# Atmega328p-AU.net
KiCad netlist of a schematic drawn in Altium Designer
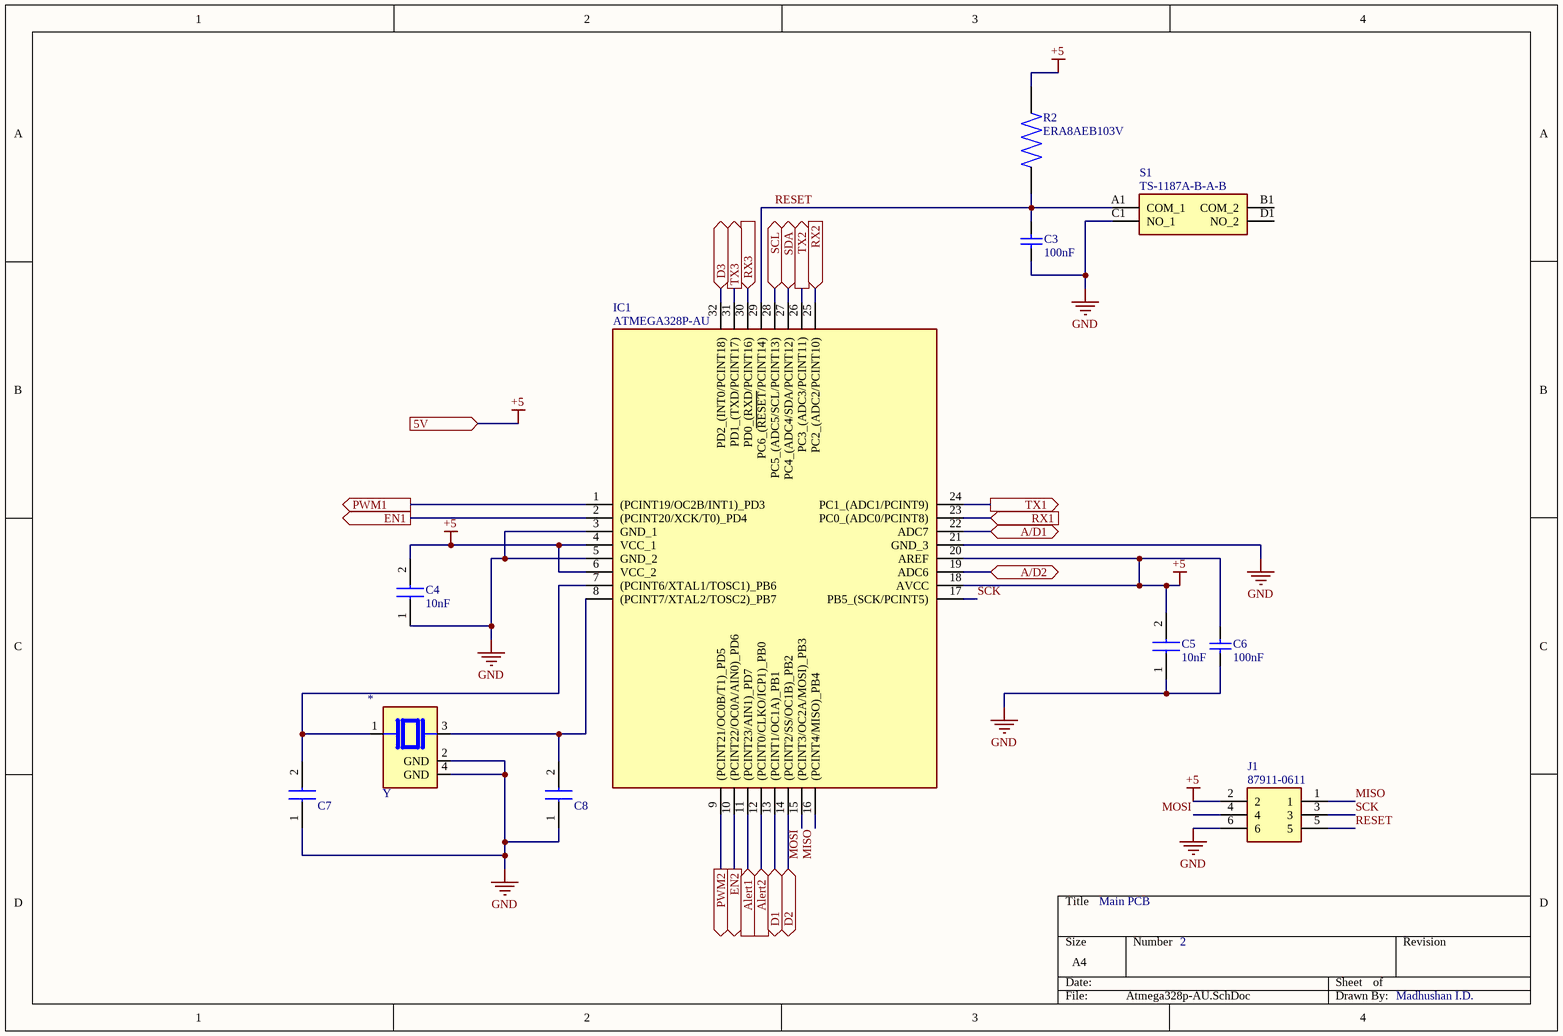
[diagram p0: Atmega328p-AU.SchDoc]

(export (version "E")
  (design (tool "Eeschema 10.0.6"))
  (components
    (comp (ref "C3")
      (value "1206GC102KAT1A")
      (footprint "AVX-1206-2_L")
      (description "Chip Capacitor, 1 nF, +/- 10%, -55 to 125 degC, 1206 (3216 Metric), RoHS, Tape and Reel")
      (fields
        (field (name "CAPACITANCE") "100nF")
        (field (name "TOLERANCE") "10%")
        (field (name "MANUFACTURER") "AVX")
      )
      (libsource (lib "Altium Content Vault") (part "CAP-NP-2"))
    )
    (comp (ref "C4")
      (value "10nF")
      (footprint "SamacSys:CAPC3216X94N")
      (description "Capacitor")
      (fields
        (field (name "MANUFACTURER_PART_NUMBER") "KAM31BR81H103KT")
        (field (name "MOUSER PART NUMBER") "581-KAM31BR81H103KT")
      )
      (libsource (lib "*") (part "KAM31BR81H103KT"))
    )
    (comp (ref "C5")
      (value "10nF")
      (footprint "SamacSys:CAPC3216X94N")
      (description "Capacitor")
      (fields
        (field (name "MANUFACTURER_PART_NUMBER") "KAM31BR81H103KT")
        (field (name "MOUSER PART NUMBER") "581-KAM31BR81H103KT")
      )
      (libsource (lib "*") (part "KAM31BR81H103KT"))
    )
    (comp (ref "C6")
      (value "1206GC102KAT1A")
      (footprint "AVX-1206-2_L")
      (description "Chip Capacitor, 1 nF, +/- 10%, -55 to 125 degC, 1206 (3216 Metric), RoHS, Tape and Reel")
      (fields
        (field (name "CAPACITANCE") "100nF")
        (field (name "TOLERANCE") "10%")
        (field (name "MANUFACTURER") "AVX")
      )
      (libsource (lib "Altium Content Vault") (part "CAP-NP-2"))
    )
    (comp (ref "C7")
      (value "C1206C220JGGACTU (22pF)")
      (footprint "SamacSys:C1206")
      (description "Capacitor")
      (fields
        (field (name "MANUFACTURER_PART_NUMBER") "C1206C220JGGACTU")
        (field (name "MOUSER PART NUMBER") "80-C1206C220JGG")
      )
      (libsource (lib "*") (part "C1206C220JGGACTU"))
    )
    (comp (ref "C8")
      (value "C1206C220JGGACTU (22pF)")
      (footprint "SamacSys:C1206")
      (description "Capacitor")
      (fields
        (field (name "MANUFACTURER_PART_NUMBER") "C1206C220JGGACTU")
        (field (name "MOUSER PART NUMBER") "80-C1206C220JGG")
      )
      (libsource (lib "*") (part "C1206C220JGGACTU"))
    )
    (comp (ref "IC1")
      (value "ATMEGA328P-AU")
      (footprint "SamacSys:QFP80P900X900X120-32N")
      (description "Integrated Circuit")
      (fields (field (name "MOUSER PART NUMBER") "556-ATMEGA328P-AU"))
      (libsource (lib "*") (part "ATMEGA328P-AU"))
    )
    (comp (ref "J1")
      (value "87911-0611")
      (footprint "SamacSys:879110611")
      (description "Connector")
      (fields (field (name "MOUSER PART NUMBER") "538-87911-0611"))
      (libsource (lib "SamacSys") (part "87911-0611"))
    )
    (comp (ref "R2")
      (value "ERA8AEB103V")
      (footprint "RES_ERA8AEB103V")
      (libsource (lib "ERA8AEB103V") (part "ERA8AEB103V"))
    )
    (comp (ref "S1")
      (value "TS-1187A-B-A-B")
      (footprint "SamacSys:TS1187ABAB")
      (description "Switch")
      (libsource (lib "*") (part "TS-1187A-B-A-B"))
    )
    (comp (ref "Y")
      (value "ABM11-16.000MHz-12-N1G-T")
      (footprint "XTAL_ABM11-16.000MHz-12-N1G-T")
      (fields (field (name "MF") "{'manufacturer': u'Abracon LLC'}") (field (name "16MHZ") "*"))
      (libsource (lib "ABM11-16.000MHz-12-N1G-T") (part "ABM11-16.000MHz-12-N1G-T"))
    )
  )
  (nets
    (net (code "1") (name "+5") (class "Default")
      (node (ref "C4") (pin "2") (pinfunction "2_2") (pintype "passive"))
      (node (ref "C5") (pin "2") (pinfunction "2_2") (pintype "passive"))
      (node (ref "C6") (pin "2") (pinfunction "2_2") (pintype "passive"))
      (node (ref "IC1") (pin "18") (pinfunction "AVCC_18") (pintype "passive"))
      (node (ref "IC1") (pin "20") (pinfunction "AREF_20") (pintype "passive"))
      (node (ref "IC1") (pin "4") (pinfunction "VCC_1_4") (pintype "passive"))
      (node (ref "IC1") (pin "6") (pinfunction "VCC_2_6") (pintype "passive"))
      (node (ref "J1") (pin "2") (pinfunction "2_2") (pintype "passive"))
      (node (ref "R2") (pin "2") (pinfunction "2_2") (pintype "passive"))
    )
    (net (code "2") (name "/Alert1") (class "Default")
      (node (ref "IC1") (pin "11") (pinfunction "(PCINT23/AIN1)_PD7_11") (pintype "passive"))
    )
    (net (code "3") (name "/Alert2") (class "Default")
      (node (ref "IC1") (pin "12") (pinfunction "(PCINT0/CLKO/ICP1)_PB0_12") (pintype "passive"))
    )
    (net (code "4") (name "/A{slash}D1") (class "Default")
      (node (ref "IC1") (pin "22") (pinfunction "ADC7_22") (pintype "passive"))
    )
    (net (code "5") (name "/A{slash}D2") (class "Default")
      (node (ref "IC1") (pin "19") (pinfunction "ADC6_19") (pintype "passive"))
    )
    (net (code "6") (name "/D1") (class "Default")
      (node (ref "IC1") (pin "13") (pinfunction "(PCINT1/OC1A)_PB1_13") (pintype "passive"))
    )
    (net (code "7") (name "/D2") (class "Default")
      (node (ref "IC1") (pin "14") (pinfunction "(PCINT2/SS/OC1B)_PB2_14") (pintype "passive"))
    )
    (net (code "8") (name "/D3") (class "Default")
      (node (ref "IC1") (pin "32") (pinfunction "PD2_(INT0/PCINT18)_32") (pintype "passive"))
    )
    (net (code "9") (name "/EN1") (class "Default")
      (node (ref "IC1") (pin "2") (pinfunction "(PCINT20/XCK/T0)_PD4_2") (pintype "passive"))
    )
    (net (code "10") (name "/EN2") (class "Default")
      (node (ref "IC1") (pin "10") (pinfunction "(PCINT22/OC0A/AIN0)_PD6_10") (pintype "passive"))
    )
    (net (code "11") (name "/MISO") (class "Default")
      (node (ref "IC1") (pin "16") (pinfunction "(PCINT4/MISO)_PB4_16") (pintype "passive"))
      (node (ref "J1") (pin "1") (pinfunction "1_1") (pintype "passive"))
    )
    (net (code "12") (name "/MOSI") (class "Default")
      (node (ref "IC1") (pin "15") (pinfunction "(PCINT3/OC2A/MOSI)_PB3_15") (pintype "passive"))
      (node (ref "J1") (pin "4") (pinfunction "4_4") (pintype "passive"))
    )
    (net (code "13") (name "/PWM1") (class "Default")
      (node (ref "IC1") (pin "1") (pinfunction "(PCINT19/OC2B/INT1)_PD3_1") (pintype "passive"))
    )
    (net (code "14") (name "/PWM2") (class "Default")
      (node (ref "IC1") (pin "9") (pinfunction "(PCINT21/OC0B/T1)_PD5_9") (pintype "passive"))
    )
    (net (code "15") (name "/RESET") (class "Default")
      (node (ref "C3") (pin "2") (pinfunction "2_2") (pintype "passive"))
      (node (ref "IC1") (pin "29") (pinfunction "PC6_(~{RESET}/PCINT14)_29") (pintype "passive"))
      (node (ref "J1") (pin "5") (pinfunction "5_5") (pintype "passive"))
      (node (ref "R2") (pin "1") (pinfunction "1_1") (pintype "passive"))
      (node (ref "S1") (pin "A1") (pinfunction "COM_1_A1") (pintype "passive"))
    )
    (net (code "16") (name "/RX1") (class "Default")
      (node (ref "IC1") (pin "23") (pinfunction "PC0_(ADC0/PCINT8)_23") (pintype "passive"))
    )
    (net (code "17") (name "/RX2") (class "Default")
      (node (ref "IC1") (pin "25") (pinfunction "PC2_(ADC2/PCINT10)_25") (pintype "passive"))
    )
    (net (code "18") (name "/RX3") (class "Default")
      (node (ref "IC1") (pin "30") (pinfunction "PD0_(RXD/PCINT16)_30") (pintype "passive"))
    )
    (net (code "19") (name "/SCK") (class "Default")
      (node (ref "IC1") (pin "17") (pinfunction "PB5_(SCK/PCINT5)_17") (pintype "passive"))
      (node (ref "J1") (pin "3") (pinfunction "3_3") (pintype "passive"))
    )
    (net (code "20") (name "/SCL") (class "Default")
      (node (ref "IC1") (pin "28") (pinfunction "PC5_(ADC5/SCL/PCINT13)_28") (pintype "passive"))
    )
    (net (code "21") (name "/SDA") (class "Default")
      (node (ref "IC1") (pin "27") (pinfunction "PC4_(ADC4/SDA/PCINT12)_27") (pintype "passive"))
    )
    (net (code "22") (name "/TX1") (class "Default")
      (node (ref "IC1") (pin "24") (pinfunction "PC1_(ADC1/PCINT9)_24") (pintype "passive"))
    )
    (net (code "23") (name "/TX2") (class "Default")
      (node (ref "IC1") (pin "26") (pinfunction "PC3_(ADC3/PCINT11)_26") (pintype "passive"))
    )
    (net (code "24") (name "/TX3") (class "Default")
      (node (ref "IC1") (pin "31") (pinfunction "PD1_(TXD/PCINT17)_31") (pintype "passive"))
    )
    (net (code "25") (name "GND") (class "Default")
      (node (ref "C3") (pin "1") (pinfunction "1_1") (pintype "passive"))
      (node (ref "C4") (pin "1") (pinfunction "1_1") (pintype "passive"))
      (node (ref "C5") (pin "1") (pinfunction "1_1") (pintype "passive"))
      (node (ref "C6") (pin "1") (pinfunction "1_1") (pintype "passive"))
      (node (ref "C7") (pin "1") (pinfunction "1_1") (pintype "passive"))
      (node (ref "C8") (pin "1") (pinfunction "1_1") (pintype "passive"))
      (node (ref "IC1") (pin "21") (pinfunction "GND_3_21") (pintype "passive"))
      (node (ref "IC1") (pin "3") (pinfunction "GND_1_3") (pintype "passive"))
      (node (ref "IC1") (pin "5") (pinfunction "GND_2_5") (pintype "passive"))
      (node (ref "J1") (pin "6") (pinfunction "6_6") (pintype "passive"))
      (node (ref "S1") (pin "C1") (pinfunction "NO_1_C1") (pintype "passive"))
      (node (ref "Y") (pin "2") (pinfunction "GND_2") (pintype "power_in"))
      (node (ref "Y") (pin "4") (pinfunction "GND_4") (pintype "power_in"))
    )
    (net (code "26") (name "Net-(IC1-(PCINT6{slash}XTAL1{slash}TOSC1)_PB6)") (class "Default")
      (node (ref "C7") (pin "2") (pinfunction "2_2") (pintype "passive"))
      (node (ref "IC1") (pin "7") (pinfunction "(PCINT6/XTAL1/TOSC1)_PB6_7") (pintype "passive"))
      (node (ref "Y") (pin "1") (pinfunction "1_1") (pintype "passive"))
    )
    (net (code "27") (name "Net-(IC1-(PCINT7{slash}XTAL2{slash}TOSC2)_PB7)") (class "Default")
      (node (ref "C8") (pin "2") (pinfunction "2_2") (pintype "passive"))
      (node (ref "IC1") (pin "8") (pinfunction "(PCINT7/XTAL2/TOSC2)_PB7_8") (pintype "passive"))
      (node (ref "Y") (pin "3") (pinfunction "2_3") (pintype "passive"))
    )
    (net (code "28") (name "unconnected-(S1-COM_2-PadB1)") (class "Default")
      (node (ref "S1") (pin "B1") (pinfunction "COM_2_B1") (pintype "passive"))
    )
    (net (code "29") (name "unconnected-(S1-NO_2-PadD1)") (class "Default")
      (node (ref "S1") (pin "D1") (pinfunction "NO_2_D1") (pintype "passive"))
    )
  )
)
